# clock_eagle_1.net
KiCad netlist of a schematic drawn in Altium Designer
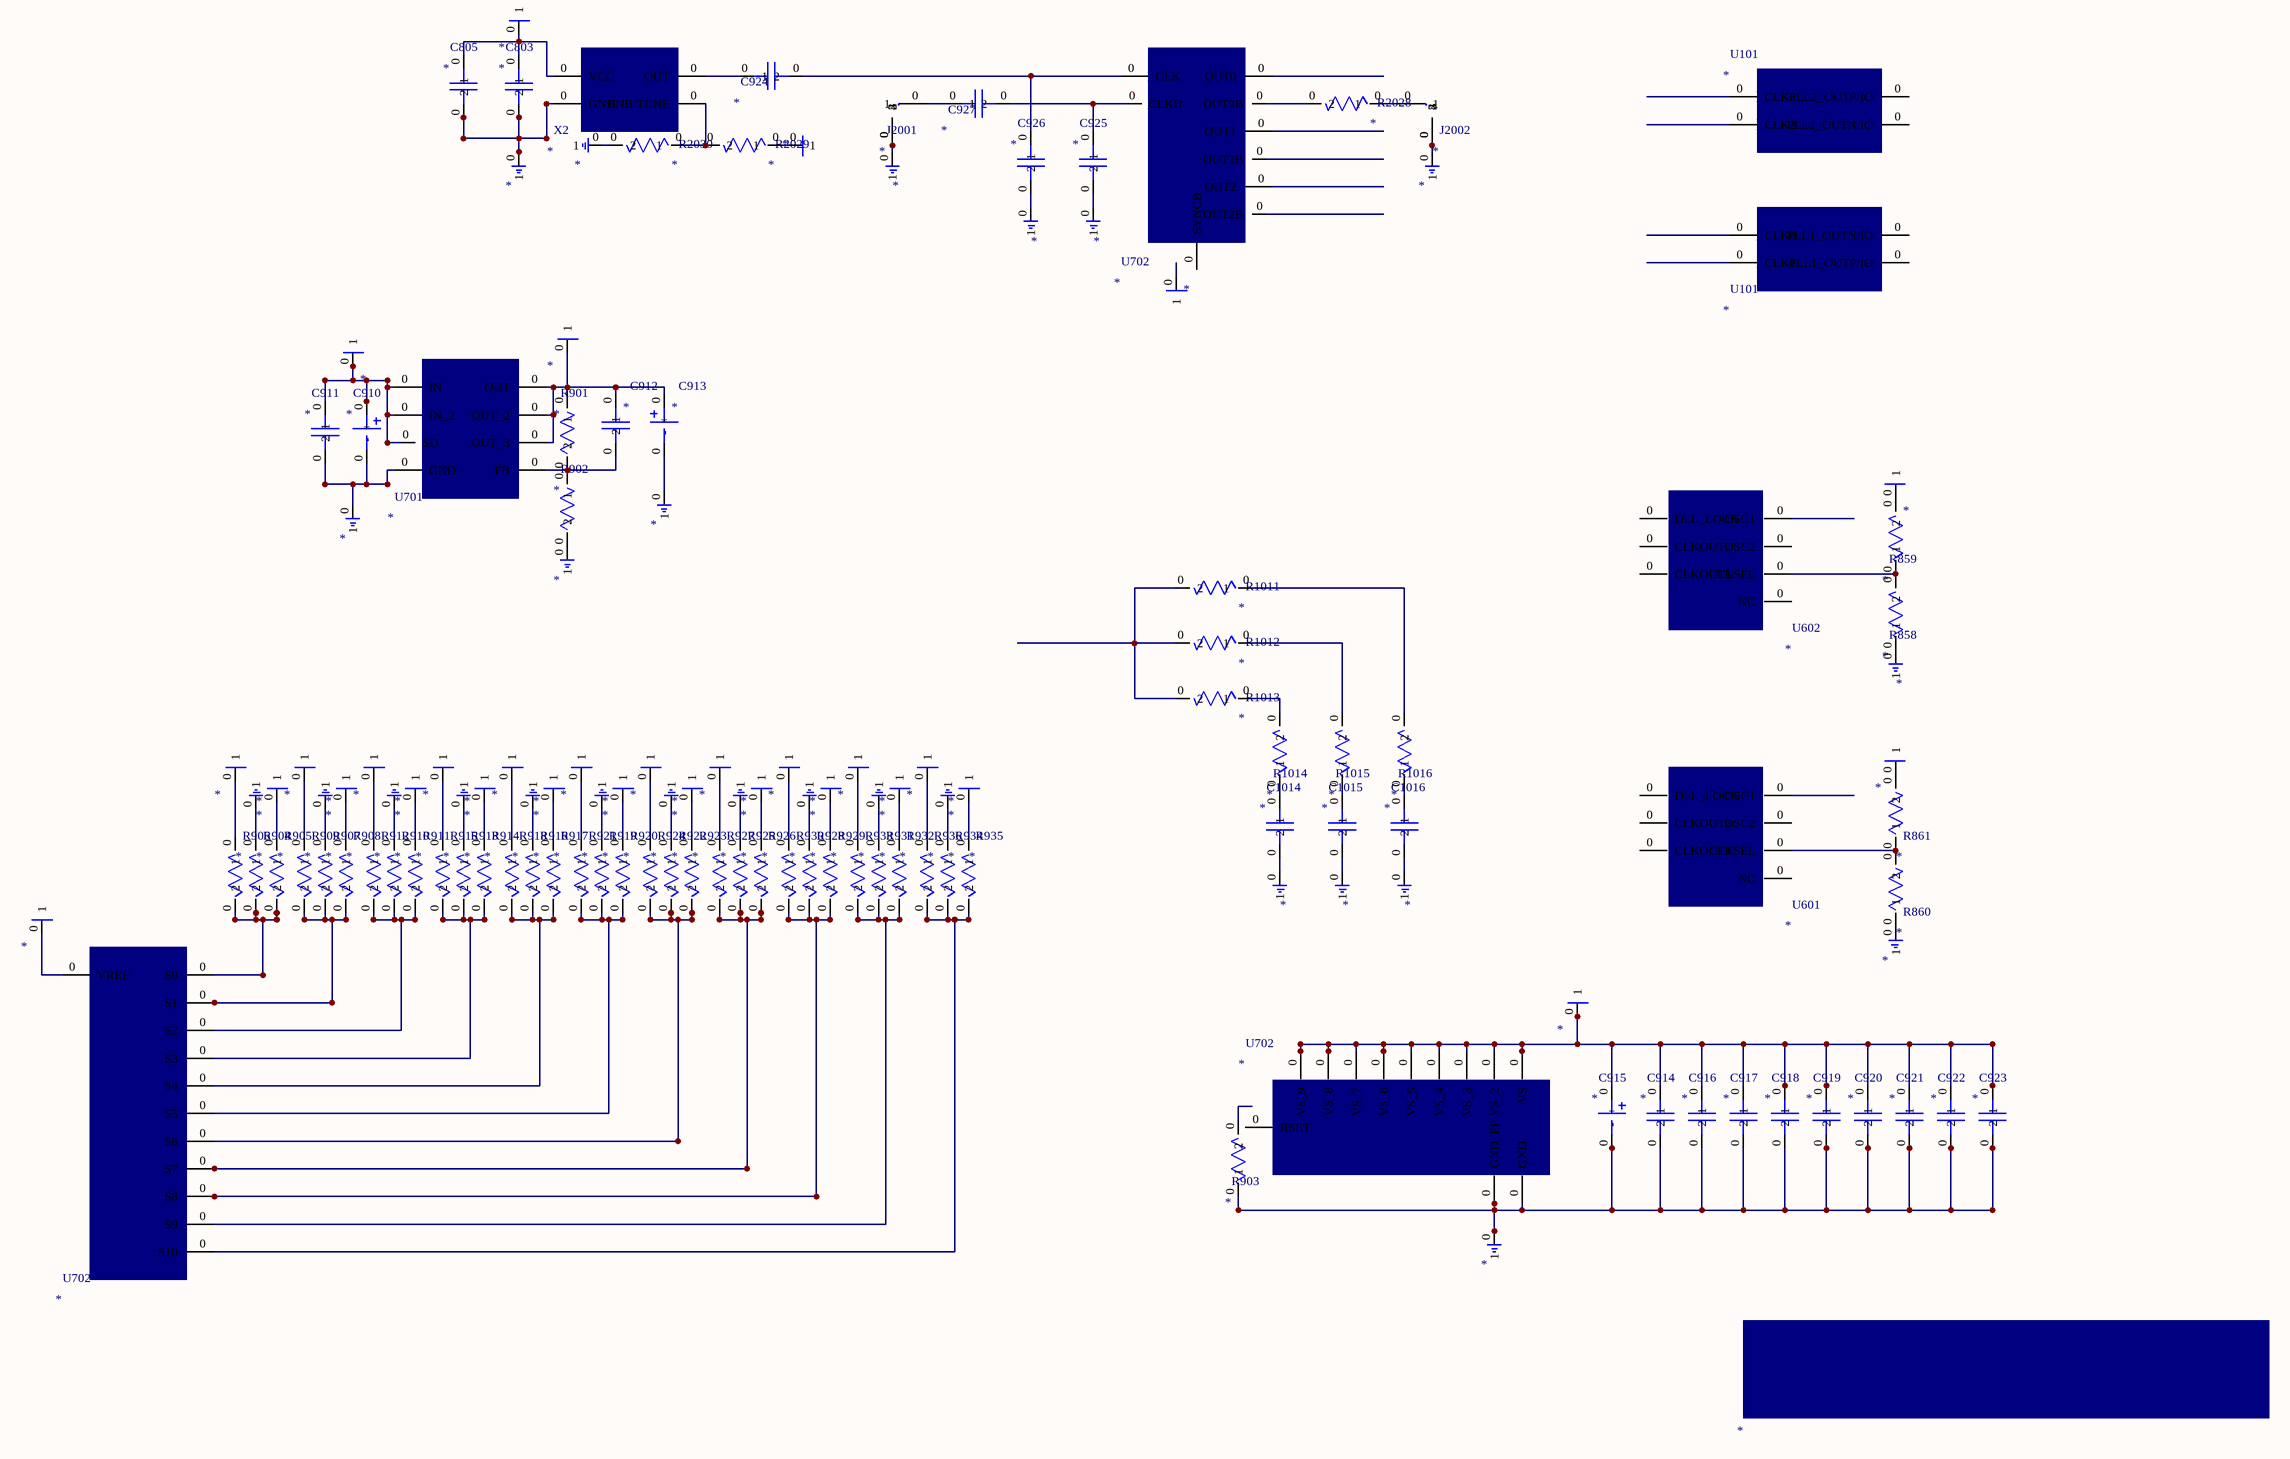
[diagram p0: clock_eagle_1.SchDoc]

(export (version "E")
  (design (tool "Eeschema 10.0.6"))
  (components
    (comp (ref "C803") (value "*") (libsource (lib "") (part "CAPACITOR-1_11")))
    (comp (ref "C805") (value "*") (libsource (lib "") (part "CAPACITOR-1_5")))
    (comp (ref "C910") (value "*") (libsource (lib "openjson") (part "CAPACITOR-2")))
    (comp (ref "C911") (value "*") (libsource (lib "") (part "CAPACITOR-1_12")))
    (comp (ref "C912") (value "*") (libsource (lib "openjson") (part "CAPACITOR-1_MIRRORED")))
    (comp (ref "C913") (value "*") (libsource (lib "openjson") (part "CAPACITOR-2_MIRRORED")))
    (comp (ref "C914") (value "*") (libsource (lib "") (part "CAPACITOR-1_2")))
    (comp (ref "C915") (value "*") (libsource (lib "") (part "CAPACITOR-2_1")))
    (comp (ref "C916") (value "*") (libsource (lib "") (part "CAPACITOR-1_1")))
    (comp (ref "C917") (value "*") (libsource (lib "") (part "CAPACITOR-1_10")))
    (comp (ref "C918") (value "*") (libsource (lib "openjson") (part "CAPACITOR-1")))
    (comp (ref "C919") (value "*") (libsource (lib "") (part "CAPACITOR-1_6")))
    (comp (ref "C920") (value "*") (libsource (lib "") (part "CAPACITOR-1_14")))
    (comp (ref "C921") (value "*") (libsource (lib "") (part "CAPACITOR-1_3")))
    (comp (ref "C922") (value "*") (libsource (lib "") (part "CAPACITOR-1_9")))
    (comp (ref "C923") (value "*") (libsource (lib "") (part "CAPACITOR-1_18")))
    (comp (ref "C924") (value "*") (libsource (lib "") (part "CAPACITOR-1_7")))
    (comp (ref "C925") (value "*") (libsource (lib "") (part "CAPACITOR-1_17")))
    (comp (ref "C926") (value "*") (libsource (lib "") (part "CAPACITOR-1_15")))
    (comp (ref "C927") (value "*") (libsource (lib "") (part "CAPACITOR-1_16")))
    (comp (ref "C1014") (value "*") (libsource (lib "") (part "CAPACITOR-1_4")))
    (comp (ref "C1015") (value "*") (libsource (lib "") (part "CAPACITOR-1_13")))
    (comp (ref "C1016") (value "*") (libsource (lib "") (part "CAPACITOR-1_8")))
    (comp (ref "CVSTITLEBLOCK-1") (value "*") (libsource (lib "openjson") (part "CVSTITLEBLOCK-1")))
    (comp (ref "GENERIC-POWER") (value "*") (libsource (lib "openjson") (part "GENERIC-POWER")))
    (comp (ref "GENERIC-POWER-0") (value "*") (libsource (lib "openjson") (part "GENERIC-POWER")))
    (comp (ref "GENERIC-POWER-5") (value "*") (libsource (lib "openjson") (part "GENERIC-POWER")))
    (comp (ref "GENERIC-POWER-13") (value "*") (libsource (lib "") (part "GENERIC-POWER_1")))
    (comp (ref "GENERIC-POWER-20") (value "*") (libsource (lib "") (part "GENERIC-POWER_1")))
    (comp (ref "GENERIC-POWER-22") (value "*") (libsource (lib "openjson") (part "GENERIC-POWER")))
    (comp (ref "GENERIC-POWER-23") (value "*") (libsource (lib "openjson") (part "GENERIC-POWER")))
    (comp (ref "GENERIC-POWER-25") (value "*") (libsource (lib "openjson") (part "GENERIC-POWER")))
    (comp (ref "GENERIC-POWER-26") (value "*") (libsource (lib "openjson") (part "GENERIC-POWER")))
    (comp (ref "GENERIC-POWER-28") (value "*") (libsource (lib "openjson") (part "GENERIC-POWER")))
    (comp (ref "GENERIC-POWER-29") (value "*") (libsource (lib "openjson") (part "GENERIC-POWER")))
    (comp (ref "GENERIC-POWER-31") (value "*") (libsource (lib "openjson") (part "GENERIC-POWER")))
    (comp (ref "GENERIC-POWER-32") (value "*") (libsource (lib "openjson") (part "GENERIC-POWER")))
    (comp (ref "GENERIC-POWER-34") (value "*") (libsource (lib "openjson") (part "GENERIC-POWER")))
    (comp (ref "GENERIC-POWER-35") (value "*") (libsource (lib "openjson") (part "GENERIC-POWER")))
    (comp (ref "GENERIC-POWER-37") (value "*") (libsource (lib "openjson") (part "GENERIC-POWER")))
    (comp (ref "GENERIC-POWER-38") (value "*") (libsource (lib "openjson") (part "GENERIC-POWER")))
    (comp (ref "GENERIC-POWER-40") (value "*") (libsource (lib "openjson") (part "GENERIC-POWER")))
    (comp (ref "GENERIC-POWER-41") (value "*") (libsource (lib "openjson") (part "GENERIC-POWER")))
    (comp (ref "GENERIC-POWER-43") (value "*") (libsource (lib "openjson") (part "GENERIC-POWER")))
    (comp (ref "GENERIC-POWER-44") (value "*") (libsource (lib "openjson") (part "GENERIC-POWER")))
    (comp (ref "GENERIC-POWER-46") (value "*") (libsource (lib "openjson") (part "GENERIC-POWER")))
    (comp (ref "GENERIC-POWER-47") (value "*") (libsource (lib "openjson") (part "GENERIC-POWER")))
    (comp (ref "GENERIC-POWER-49") (value "*") (libsource (lib "openjson") (part "GENERIC-POWER")))
    (comp (ref "GENERIC-POWER-50") (value "*") (libsource (lib "openjson") (part "GENERIC-POWER")))
    (comp (ref "GENERIC-POWER-52") (value "*") (libsource (lib "openjson") (part "GENERIC-POWER")))
    (comp (ref "GENERIC-POWER-53") (value "*") (libsource (lib "openjson") (part "GENERIC-POWER")))
    (comp (ref "GENERIC-POWER-54") (value "*") (libsource (lib "openjson") (part "GENERIC-POWER")))
    (comp (ref "GENERIC-POWER-55") (value "*") (libsource (lib "openjson") (part "GENERIC-POWER")))
    (comp (ref "GENERIC-POWER_MIRRORED")
      (value "*")
      (libsource (lib "openjson") (part "GENERIC-POWER_MIRRORED"))
    )
    (comp (ref "GENERIC-POWER_MIRRORED-11")
      (value "*")
      (libsource (lib "") (part "GENERIC-POWER_MIRRORED_1"))
    )
    (comp (ref "GND-1") (value "*") (libsource (lib "openjson") (part "GND-1")))
    (comp (ref "GND-1-6") (value "*") (libsource (lib "openjson") (part "GND-1")))
    (comp (ref "GND-1-7") (value "*") (libsource (lib "openjson") (part "GND-1")))
    (comp (ref "GND-1-8") (value "*") (libsource (lib "openjson") (part "GND-1")))
    (comp (ref "GND-1-12") (value "*") (libsource (lib "") (part "GND-1_2")))
    (comp (ref "GND-1-16") (value "*") (libsource (lib "openjson") (part "GND-1")))
    (comp (ref "GND-1-19") (value "*") (libsource (lib "openjson") (part "GND-1")))
    (comp (ref "GND-1-21") (value "*") (libsource (lib "") (part "GND-1_1")))
    (comp (ref "GND-1-24") (value "*") (libsource (lib "") (part "GND-1_1")))
    (comp (ref "GND-1-27") (value "*") (libsource (lib "") (part "GND-1_1")))
    (comp (ref "GND-1-30") (value "*") (libsource (lib "") (part "GND-1_1")))
    (comp (ref "GND-1-33") (value "*") (libsource (lib "") (part "GND-1_1")))
    (comp (ref "GND-1-36") (value "*") (libsource (lib "") (part "GND-1_1")))
    (comp (ref "GND-1-39") (value "*") (libsource (lib "") (part "GND-1_1")))
    (comp (ref "GND-1-42") (value "*") (libsource (lib "") (part "GND-1_1")))
    (comp (ref "GND-1-45") (value "*") (libsource (lib "") (part "GND-1_1")))
    (comp (ref "GND-1-48") (value "*") (libsource (lib "") (part "GND-1_1")))
    (comp (ref "GND-1-51") (value "*") (libsource (lib "") (part "GND-1_1")))
    (comp (ref "GND-1_MIRRORED") (value "*") (libsource (lib "") (part "GND-1_MIRRORED_1")))
    (comp (ref "GND-1_MIRRORED-1") (value "*") (libsource (lib "") (part "GND-1_MIRRORED_1")))
    (comp (ref "GND-1_MIRRORED-2") (value "*") (libsource (lib "") (part "GND-1_MIRRORED_1")))
    (comp (ref "GND-1_MIRRORED-3") (value "*") (libsource (lib "") (part "GND-1_MIRRORED_1")))
    (comp (ref "GND-1_MIRRORED-4") (value "*") (libsource (lib "") (part "GND-1_MIRRORED_2")))
    (comp (ref "GND-1_MIRRORED-10") (value "*") (libsource (lib "openjson") (part "GND-1_MIRRORED")))
    (comp (ref "GND-1_MIRRORED-17") (value "*") (libsource (lib "") (part "GND-1_MIRRORED_1")))
    (comp (ref "GND-1_MIRRORED-18") (value "*") (libsource (lib "") (part "GND-1_MIRRORED_1")))
    (comp (ref "J2001") (value "*") (libsource (lib "openjson") (part "SMA-5")))
    (comp (ref "J2002") (value "*") (libsource (lib "openjson") (part "SMA-5_MIRRORED")))
    (comp (ref "R858") (value "*") (libsource (lib "") (part "RESISTOR-1_MIRRORED_40")))
    (comp (ref "R859") (value "*") (libsource (lib "") (part "RESISTOR-1_MIRRORED_39")))
    (comp (ref "R860") (value "*") (libsource (lib "") (part "RESISTOR-1_3")))
    (comp (ref "R861") (value "*") (libsource (lib "") (part "RESISTOR-1_1")))
    (comp (ref "R901") (value "*") (libsource (lib "openjson") (part "RESISTOR-1")))
    (comp (ref "R902") (value "*") (libsource (lib "") (part "RESISTOR-1_2")))
    (comp (ref "R903") (value "*") (libsource (lib "") (part "RESISTOR-1_MIRRORED_22")))
    (comp (ref "R904") (value "*") (libsource (lib "") (part "RESISTOR-1_MIRRORED_28")))
    (comp (ref "R905") (value "*") (libsource (lib "") (part "RESISTOR-1_MIRRORED_25")))
    (comp (ref "R906") (value "*") (libsource (lib "") (part "RESISTOR-1_MIRRORED_35")))
    (comp (ref "R907") (value "*") (libsource (lib "") (part "RESISTOR-1_MIRRORED_20")))
    (comp (ref "R908") (value "*") (libsource (lib "") (part "RESISTOR-1_MIRRORED_37")))
    (comp (ref "R909") (value "*") (libsource (lib "") (part "RESISTOR-1_MIRRORED_34")))
    (comp (ref "R910") (value "*") (libsource (lib "") (part "RESISTOR-1_MIRRORED_31")))
    (comp (ref "R911") (value "*") (libsource (lib "") (part "RESISTOR-1_MIRRORED_32")))
    (comp (ref "R912") (value "*") (libsource (lib "") (part "RESISTOR-1_MIRRORED_38")))
    (comp (ref "R913") (value "*") (libsource (lib "") (part "RESISTOR-1_MIRRORED_30")))
    (comp (ref "R914") (value "*") (libsource (lib "") (part "RESISTOR-1_MIRRORED_1")))
    (comp (ref "R915") (value "*") (libsource (lib "") (part "RESISTOR-1_MIRRORED_4")))
    (comp (ref "R916") (value "*") (libsource (lib "") (part "RESISTOR-1_MIRRORED_21")))
    (comp (ref "R917") (value "*") (libsource (lib "") (part "RESISTOR-1_MIRRORED_8")))
    (comp (ref "R918") (value "*") (libsource (lib "") (part "RESISTOR-1_MIRRORED_10")))
    (comp (ref "R919") (value "*") (libsource (lib "") (part "RESISTOR-1_MIRRORED_18")))
    (comp (ref "R920") (value "*") (libsource (lib "") (part "RESISTOR-1_MIRRORED_11")))
    (comp (ref "R921") (value "*") (libsource (lib "") (part "RESISTOR-1_MIRRORED_15")))
    (comp (ref "R922") (value "*") (libsource (lib "") (part "RESISTOR-1_MIRRORED_16")))
    (comp (ref "R923") (value "*") (libsource (lib "") (part "RESISTOR-1_MIRRORED_29")))
    (comp (ref "R924") (value "*") (libsource (lib "") (part "RESISTOR-1_MIRRORED_7")))
    (comp (ref "R925") (value "*") (libsource (lib "") (part "RESISTOR-1_MIRRORED_5")))
    (comp (ref "R926") (value "*") (libsource (lib "openjson") (part "RESISTOR-1_MIRRORED")))
    (comp (ref "R927") (value "*") (libsource (lib "") (part "RESISTOR-1_MIRRORED_36")))
    (comp (ref "R928") (value "*") (libsource (lib "") (part "RESISTOR-1_MIRRORED_12")))
    (comp (ref "R929") (value "*") (libsource (lib "") (part "RESISTOR-1_MIRRORED_17")))
    (comp (ref "R930") (value "*") (libsource (lib "") (part "RESISTOR-1_MIRRORED_27")))
    (comp (ref "R931") (value "*") (libsource (lib "") (part "RESISTOR-1_MIRRORED_24")))
    (comp (ref "R932") (value "*") (libsource (lib "") (part "RESISTOR-1_MIRRORED_33")))
    (comp (ref "R933") (value "*") (libsource (lib "") (part "RESISTOR-1_MIRRORED_41")))
    (comp (ref "R934") (value "*") (libsource (lib "") (part "RESISTOR-1_MIRRORED_42")))
    (comp (ref "R935") (value "*") (libsource (lib "") (part "RESISTOR-1_MIRRORED_14")))
    (comp (ref "R936") (value "*") (libsource (lib "") (part "RESISTOR-1_MIRRORED_23")))
    (comp (ref "R1011") (value "*") (libsource (lib "") (part "RESISTOR-1_MIRRORED_26")))
    (comp (ref "R1012") (value "*") (libsource (lib "") (part "RESISTOR-1_MIRRORED_44")))
    (comp (ref "R1013") (value "*") (libsource (lib "") (part "RESISTOR-1_MIRRORED_3")))
    (comp (ref "R1014") (value "*") (libsource (lib "") (part "RESISTOR-1_MIRRORED_13")))
    (comp (ref "R1015") (value "*") (libsource (lib "") (part "RESISTOR-1_MIRRORED_43")))
    (comp (ref "R1016") (value "*") (libsource (lib "") (part "RESISTOR-1_MIRRORED_19")))
    (comp (ref "R2028") (value "*") (libsource (lib "") (part "RESISTOR-1_MIRRORED_6")))
    (comp (ref "R2029") (value "*") (libsource (lib "") (part "RESISTOR-1_MIRRORED_2")))
    (comp (ref "R2030") (value "*") (libsource (lib "") (part "RESISTOR-1_MIRRORED_9")))
    (comp (ref "U101") (value "*") (libsource (lib "openjson") (part "EP1C12-PQ240-CLKA")))
    (comp (ref "U101-9") (value "*") (libsource (lib "openjson") (part "EP1C12-PQ240-CLKB_MIRRORED")))
    (comp (ref "U601") (value "*") (libsource (lib "openjson") (part "AD986X-CLK_MIRRORED")))
    (comp (ref "U602") (value "*") (libsource (lib "") (part "AD986X-CLK_MIRRORED_1")))
    (comp (ref "U701") (value "*") (libsource (lib "openjson") (part "ADP3336")))
    (comp (ref "U702") (value "*") (libsource (lib "openjson") (part "AD9513-CLK")))
    (comp (ref "U702-14") (value "*") (libsource (lib "openjson") (part "AD9513-CTRL")))
    (comp (ref "U702-15") (value "*") (libsource (lib "openjson") (part "AD9513-PWR")))
    (comp (ref "X2") (value "*") (libsource (lib "openjson") (part "VCTCXO")))
  )
  (nets
    (net (code "1") (name "Net-(C803-1)") (class "Default")
      (node (ref "C803") (pin "0") (pinfunction "1_0") (pintype "passive"))
      (node (ref "C805") (pin "0") (pinfunction "1_0") (pintype "passive"))
      (node (ref "GENERIC-POWER") (pin "0") (pinfunction "1_0") (pintype "passive"))
      (node (ref "X2") (pin "0") (pinfunction "VCC_0") (pintype "passive"))
    )
    (net (code "2") (name "Net-(C803-2)") (class "Default")
      (node (ref "C803") (pin "0") (pinfunction "2_0") (pintype "passive"))
      (node (ref "C805") (pin "0") (pinfunction "2_0") (pintype "passive"))
      (node (ref "GND-1") (pin "0") (pinfunction "1_0") (pintype "passive"))
      (node (ref "X2") (pin "0") (pinfunction "GND_0") (pintype "passive"))
    )
    (net (code "3") (name "Net-(C910-+)") (class "Default")
      (node (ref "C910") (pin "0") (pinfunction "+_0") (pintype "passive"))
      (node (ref "C911") (pin "0") (pinfunction "1_0") (pintype "passive"))
      (node (ref "GENERIC-POWER_MIRRORED") (pin "0") (pinfunction "1_0") (pintype "passive"))
      (node (ref "U701") (pin "0") (pinfunction "IN_0") (pintype "passive"))
    )
    (net (code "4") (name "Net-(C910--)") (class "Default")
      (node (ref "C910") (pin "0") (pinfunction "-_0") (pintype "passive"))
      (node (ref "C911") (pin "0") (pinfunction "2_0") (pintype "passive"))
      (node (ref "GND-1-6") (pin "0") (pinfunction "1_0") (pintype "passive"))
      (node (ref "U701") (pin "0") (pinfunction "GND_0") (pintype "passive"))
    )
    (net (code "5") (name "Net-(C912-1)") (class "Default")
      (node (ref "C912") (pin "0") (pinfunction "1_0") (pintype "passive"))
      (node (ref "C913") (pin "0") (pinfunction "+_0") (pintype "passive"))
      (node (ref "GENERIC-POWER-5") (pin "0") (pinfunction "1_0") (pintype "passive"))
      (node (ref "R901") (pin "0") (pinfunction "1_0") (pintype "passive"))
      (node (ref "U701") (pin "0") (pinfunction "OUT_0") (pintype "passive"))
    )
    (net (code "6") (name "Net-(C912-2)") (class "Default")
      (node (ref "C912") (pin "0") (pinfunction "2_0") (pintype "passive"))
      (node (ref "R901") (pin "0") (pinfunction "2_0") (pintype "passive"))
      (node (ref "R902") (pin "0") (pinfunction "1_0") (pintype "passive"))
      (node (ref "U701") (pin "0") (pinfunction "FB_0") (pintype "passive"))
    )
    (net (code "7") (name "Net-(C913--)") (class "Default")
      (node (ref "C913") (pin "0") (pinfunction "-_0") (pintype "passive"))
      (node (ref "GND-1-8") (pin "0") (pinfunction "1_0") (pintype "passive"))
    )
    (net (code "8") (name "Net-(C914-1)") (class "Default")
      (node (ref "C914") (pin "0") (pinfunction "1_0") (pintype "passive"))
      (node (ref "C915") (pin "0") (pinfunction "+_0") (pintype "passive"))
      (node (ref "C916") (pin "0") (pinfunction "1_0") (pintype "passive"))
      (node (ref "C917") (pin "0") (pinfunction "1_0") (pintype "passive"))
      (node (ref "C918") (pin "0") (pinfunction "1_0") (pintype "passive"))
      (node (ref "C919") (pin "0") (pinfunction "1_0") (pintype "passive"))
      (node (ref "C920") (pin "0") (pinfunction "1_0") (pintype "passive"))
      (node (ref "C921") (pin "0") (pinfunction "1_0") (pintype "passive"))
      (node (ref "C922") (pin "0") (pinfunction "1_0") (pintype "passive"))
      (node (ref "C923") (pin "0") (pinfunction "1_0") (pintype "passive"))
      (node (ref "GENERIC-POWER-55") (pin "0") (pinfunction "1_0") (pintype "passive"))
      (node (ref "U702-15") (pin "0") (pinfunction "VS_9_0") (pintype "passive"))
    )
    (net (code "9") (name "Net-(C914-2)") (class "Default")
      (node (ref "C914") (pin "0") (pinfunction "2_0") (pintype "passive"))
      (node (ref "C915") (pin "0") (pinfunction "-_0") (pintype "passive"))
      (node (ref "C916") (pin "0") (pinfunction "2_0") (pintype "passive"))
      (node (ref "C917") (pin "0") (pinfunction "2_0") (pintype "passive"))
      (node (ref "C918") (pin "0") (pinfunction "2_0") (pintype "passive"))
      (node (ref "C919") (pin "0") (pinfunction "2_0") (pintype "passive"))
      (node (ref "C920") (pin "0") (pinfunction "2_0") (pintype "passive"))
      (node (ref "C921") (pin "0") (pinfunction "2_0") (pintype "passive"))
      (node (ref "C922") (pin "0") (pinfunction "2_0") (pintype "passive"))
      (node (ref "C923") (pin "0") (pinfunction "2_0") (pintype "passive"))
      (node (ref "GND-1-16") (pin "0") (pinfunction "1_0") (pintype "passive"))
      (node (ref "R903") (pin "0") (pinfunction "1_0") (pintype "passive"))
      (node (ref "U702-15") (pin "0") (pinfunction "GND_0") (pintype "passive"))
    )
    (net (code "10") (name "Net-(C924-1)") (class "Default")
      (node (ref "C924") (pin "0") (pinfunction "1_0") (pintype "passive"))
      (node (ref "X2") (pin "0") (pinfunction "OUT_0") (pintype "passive"))
    )
    (net (code "11") (name "Net-(C924-2)") (class "Default")
      (node (ref "C924") (pin "0") (pinfunction "2_0") (pintype "passive"))
      (node (ref "C926") (pin "0") (pinfunction "1_0") (pintype "passive"))
      (node (ref "U702") (pin "0") (pinfunction "CLK_0") (pintype "passive"))
    )
    (net (code "12") (name "Net-(C925-1)") (class "Default")
      (node (ref "C925") (pin "0") (pinfunction "1_0") (pintype "passive"))
      (node (ref "C927") (pin "0") (pinfunction "2_0") (pintype "passive"))
      (node (ref "U702") (pin "0") (pinfunction "CLKB_0") (pintype "passive"))
    )
    (net (code "13") (name "Net-(C925-2)") (class "Default")
      (node (ref "C925") (pin "0") (pinfunction "2_0") (pintype "passive"))
      (node (ref "GND-1_MIRRORED-17") (pin "0") (pinfunction "1_0") (pintype "passive"))
    )
    (net (code "14") (name "Net-(C926-2)") (class "Default")
      (node (ref "C926") (pin "0") (pinfunction "2_0") (pintype "passive"))
      (node (ref "GND-1_MIRRORED-18") (pin "0") (pinfunction "1_0") (pintype "passive"))
    )
    (net (code "15") (name "Net-(C927-1)") (class "Default")
      (node (ref "C927") (pin "0") (pinfunction "1_0") (pintype "passive"))
      (node (ref "J2001") (pin "0") (pinfunction "1_0") (pintype "passive"))
    )
    (net (code "16") (name "Net-(C1014-1)") (class "Default")
      (node (ref "C1014") (pin "0") (pinfunction "1_0") (pintype "passive"))
      (node (ref "R1014") (pin "0") (pinfunction "1_0") (pintype "passive"))
    )
    (net (code "17") (name "Net-(C1014-2)") (class "Default")
      (node (ref "C1014") (pin "0") (pinfunction "2_0") (pintype "passive"))
      (node (ref "GND-1_MIRRORED") (pin "0") (pinfunction "1_0") (pintype "passive"))
    )
    (net (code "18") (name "Net-(C1015-1)") (class "Default")
      (node (ref "C1015") (pin "0") (pinfunction "1_0") (pintype "passive"))
      (node (ref "R1015") (pin "0") (pinfunction "1_0") (pintype "passive"))
    )
    (net (code "19") (name "Net-(C1015-2)") (class "Default")
      (node (ref "C1015") (pin "0") (pinfunction "2_0") (pintype "passive"))
      (node (ref "GND-1_MIRRORED-1") (pin "0") (pinfunction "1_0") (pintype "passive"))
    )
    (net (code "20") (name "Net-(C1016-1)") (class "Default")
      (node (ref "C1016") (pin "0") (pinfunction "1_0") (pintype "passive"))
      (node (ref "R1016") (pin "0") (pinfunction "1_0") (pintype "passive"))
    )
    (net (code "21") (name "Net-(C1016-2)") (class "Default")
      (node (ref "C1016") (pin "0") (pinfunction "2_0") (pintype "passive"))
      (node (ref "GND-1_MIRRORED-2") (pin "0") (pinfunction "1_0") (pintype "passive"))
    )
    (net (code "22") (name "Net-(GENERIC-POWER-0-1)") (class "Default")
      (node (ref "GENERIC-POWER-0") (pin "0") (pinfunction "1_0") (pintype "passive"))
      (node (ref "R2029") (pin "0") (pinfunction "1_0") (pintype "passive"))
    )
    (net (code "23") (name "Net-(GENERIC-POWER-13-1)") (class "Default")
      (node (ref "GENERIC-POWER-13") (pin "0") (pinfunction "1_0") (pintype "passive"))
      (node (ref "R861") (pin "0") (pinfunction "2_0") (pintype "passive"))
    )
    (net (code "24") (name "Net-(GENERIC-POWER-22-1)") (class "Default")
      (node (ref "GENERIC-POWER-22") (pin "0") (pinfunction "1_0") (pintype "passive"))
      (node (ref "R905") (pin "0") (pinfunction "1_0") (pintype "passive"))
    )
    (net (code "25") (name "Net-(GENERIC-POWER-23-1)") (class "Default")
      (node (ref "GENERIC-POWER-23") (pin "0") (pinfunction "1_0") (pintype "passive"))
      (node (ref "R906") (pin "0") (pinfunction "1_0") (pintype "passive"))
    )
    (net (code "26") (name "Net-(GENERIC-POWER-25-1)") (class "Default")
      (node (ref "GENERIC-POWER-25") (pin "0") (pinfunction "1_0") (pintype "passive"))
      (node (ref "R908") (pin "0") (pinfunction "1_0") (pintype "passive"))
    )
    (net (code "27") (name "Net-(GENERIC-POWER-26-1)") (class "Default")
      (node (ref "GENERIC-POWER-26") (pin "0") (pinfunction "1_0") (pintype "passive"))
      (node (ref "R909") (pin "0") (pinfunction "1_0") (pintype "passive"))
    )
    (net (code "28") (name "Net-(GENERIC-POWER-28-1)") (class "Default")
      (node (ref "GENERIC-POWER-28") (pin "0") (pinfunction "1_0") (pintype "passive"))
      (node (ref "R911") (pin "0") (pinfunction "1_0") (pintype "passive"))
    )
    (net (code "29") (name "Net-(GENERIC-POWER-29-1)") (class "Default")
      (node (ref "GENERIC-POWER-29") (pin "0") (pinfunction "1_0") (pintype "passive"))
      (node (ref "R912") (pin "0") (pinfunction "1_0") (pintype "passive"))
    )
    (net (code "30") (name "Net-(GENERIC-POWER-31-1)") (class "Default")
      (node (ref "GENERIC-POWER-31") (pin "0") (pinfunction "1_0") (pintype "passive"))
      (node (ref "R914") (pin "0") (pinfunction "1_0") (pintype "passive"))
    )
    (net (code "31") (name "Net-(GENERIC-POWER-32-1)") (class "Default")
      (node (ref "GENERIC-POWER-32") (pin "0") (pinfunction "1_0") (pintype "passive"))
      (node (ref "R915") (pin "0") (pinfunction "1_0") (pintype "passive"))
    )
    (net (code "32") (name "Net-(GENERIC-POWER-34-1)") (class "Default")
      (node (ref "GENERIC-POWER-34") (pin "0") (pinfunction "1_0") (pintype "passive"))
      (node (ref "R917") (pin "0") (pinfunction "1_0") (pintype "passive"))
    )
    (net (code "33") (name "Net-(GENERIC-POWER-35-1)") (class "Default")
      (node (ref "GENERIC-POWER-35") (pin "0") (pinfunction "1_0") (pintype "passive"))
      (node (ref "R918") (pin "0") (pinfunction "1_0") (pintype "passive"))
    )
    (net (code "34") (name "Net-(GENERIC-POWER-37-1)") (class "Default")
      (node (ref "GENERIC-POWER-37") (pin "0") (pinfunction "1_0") (pintype "passive"))
      (node (ref "R920") (pin "0") (pinfunction "1_0") (pintype "passive"))
    )
    (net (code "35") (name "Net-(GENERIC-POWER-38-1)") (class "Default")
      (node (ref "GENERIC-POWER-38") (pin "0") (pinfunction "1_0") (pintype "passive"))
      (node (ref "R921") (pin "0") (pinfunction "1_0") (pintype "passive"))
    )
    (net (code "36") (name "Net-(GENERIC-POWER-40-1)") (class "Default")
      (node (ref "GENERIC-POWER-40") (pin "0") (pinfunction "1_0") (pintype "passive"))
      (node (ref "R923") (pin "0") (pinfunction "1_0") (pintype "passive"))
    )
    (net (code "37") (name "Net-(GENERIC-POWER-41-1)") (class "Default")
      (node (ref "GENERIC-POWER-41") (pin "0") (pinfunction "1_0") (pintype "passive"))
      (node (ref "R924") (pin "0") (pinfunction "1_0") (pintype "passive"))
    )
    (net (code "38") (name "Net-(GENERIC-POWER-43-1)") (class "Default")
      (node (ref "GENERIC-POWER-43") (pin "0") (pinfunction "1_0") (pintype "passive"))
      (node (ref "R926") (pin "0") (pinfunction "1_0") (pintype "passive"))
    )
    (net (code "39") (name "Net-(GENERIC-POWER-44-1)") (class "Default")
      (node (ref "GENERIC-POWER-44") (pin "0") (pinfunction "1_0") (pintype "passive"))
      (node (ref "R927") (pin "0") (pinfunction "1_0") (pintype "passive"))
    )
    (net (code "40") (name "Net-(GENERIC-POWER-46-1)") (class "Default")
      (node (ref "GENERIC-POWER-46") (pin "0") (pinfunction "1_0") (pintype "passive"))
      (node (ref "R929") (pin "0") (pinfunction "1_0") (pintype "passive"))
    )
    (net (code "41") (name "Net-(GENERIC-POWER-47-1)") (class "Default")
      (node (ref "GENERIC-POWER-47") (pin "0") (pinfunction "1_0") (pintype "passive"))
      (node (ref "R930") (pin "0") (pinfunction "1_0") (pintype "passive"))
    )
    (net (code "42") (name "Net-(GENERIC-POWER-49-1)") (class "Default")
      (node (ref "GENERIC-POWER-49") (pin "0") (pinfunction "1_0") (pintype "passive"))
      (node (ref "R932") (pin "0") (pinfunction "1_0") (pintype "passive"))
    )
    (net (code "43") (name "Net-(GENERIC-POWER-50-1)") (class "Default")
      (node (ref "GENERIC-POWER-50") (pin "0") (pinfunction "1_0") (pintype "passive"))
      (node (ref "R933") (pin "0") (pinfunction "1_0") (pintype "passive"))
    )
    (net (code "44") (name "Net-(GENERIC-POWER-52-1)") (class "Default")
      (node (ref "GENERIC-POWER-52") (pin "0") (pinfunction "1_0") (pintype "passive"))
      (node (ref "R935") (pin "0") (pinfunction "1_0") (pintype "passive"))
    )
    (net (code "45") (name "Net-(GENERIC-POWER-53-1)") (class "Default")
      (node (ref "GENERIC-POWER-53") (pin "0") (pinfunction "1_0") (pintype "passive"))
      (node (ref "R936") (pin "0") (pinfunction "1_0") (pintype "passive"))
    )
    (net (code "46") (name "Net-(GENERIC-POWER-54-1)") (class "Default")
      (node (ref "GENERIC-POWER-54") (pin "0") (pinfunction "1_0") (pintype "passive"))
      (node (ref "U702-14") (pin "0") (pinfunction "VREF_0") (pintype "passive"))
    )
    (net (code "47") (name "Net-(GENERIC-POWER_MIRRORED-11-1)") (class "Default")
      (node (ref "GENERIC-POWER_MIRRORED-11") (pin "0") (pinfunction "1_0") (pintype "passive"))
      (node (ref "R859") (pin "0") (pinfunction "2_0") (pintype "passive"))
    )
    (net (code "48") (name "Net-(GND-1-7-1)") (class "Default")
      (node (ref "GND-1-7") (pin "0") (pinfunction "1_0") (pintype "passive"))
      (node (ref "R902") (pin "0") (pinfunction "2_0") (pintype "passive"))
    )
    (net (code "49") (name "Net-(GND-1-12-1)") (class "Default")
      (node (ref "GND-1-12") (pin "0") (pinfunction "1_0") (pintype "passive"))
      (node (ref "R860") (pin "0") (pinfunction "1_0") (pintype "passive"))
    )
    (net (code "50") (name "Net-(GND-1-19-1)") (class "Default")
      (node (ref "GND-1-19") (pin "0") (pinfunction "1_0") (pintype "passive"))
      (node (ref "J2002") (pin "0") (pinfunction "2_0") (pintype "passive"))
    )
    (net (code "51") (name "Net-(GND-1-21-1)") (class "Default")
      (node (ref "GND-1-21") (pin "0") (pinfunction "1_0") (pintype "passive"))
      (node (ref "R904") (pin "0") (pinfunction "1_0") (pintype "passive"))
    )
    (net (code "52") (name "Net-(GND-1-24-1)") (class "Default")
      (node (ref "GND-1-24") (pin "0") (pinfunction "1_0") (pintype "passive"))
      (node (ref "R907") (pin "0") (pinfunction "1_0") (pintype "passive"))
    )
    (net (code "53") (name "Net-(GND-1-27-1)") (class "Default")
      (node (ref "GND-1-27") (pin "0") (pinfunction "1_0") (pintype "passive"))
      (node (ref "R910") (pin "0") (pinfunction "1_0") (pintype "passive"))
    )
    (net (code "54") (name "Net-(GND-1-30-1)") (class "Default")
      (node (ref "GND-1-30") (pin "0") (pinfunction "1_0") (pintype "passive"))
      (node (ref "R913") (pin "0") (pinfunction "1_0") (pintype "passive"))
    )
    (net (code "55") (name "Net-(GND-1-33-1)") (class "Default")
      (node (ref "GND-1-33") (pin "0") (pinfunction "1_0") (pintype "passive"))
      (node (ref "R916") (pin "0") (pinfunction "1_0") (pintype "passive"))
    )
    (net (code "56") (name "Net-(GND-1-36-1)") (class "Default")
      (node (ref "GND-1-36") (pin "0") (pinfunction "1_0") (pintype "passive"))
      (node (ref "R919") (pin "0") (pinfunction "1_0") (pintype "passive"))
    )
    (net (code "57") (name "Net-(GND-1-39-1)") (class "Default")
      (node (ref "GND-1-39") (pin "0") (pinfunction "1_0") (pintype "passive"))
      (node (ref "R922") (pin "0") (pinfunction "1_0") (pintype "passive"))
    )
    (net (code "58") (name "Net-(GND-1-42-1)") (class "Default")
      (node (ref "GND-1-42") (pin "0") (pinfunction "1_0") (pintype "passive"))
      (node (ref "R925") (pin "0") (pinfunction "1_0") (pintype "passive"))
    )
    (net (code "59") (name "Net-(GND-1-45-1)") (class "Default")
      (node (ref "GND-1-45") (pin "0") (pinfunction "1_0") (pintype "passive"))
      (node (ref "R928") (pin "0") (pinfunction "1_0") (pintype "passive"))
    )
    (net (code "60") (name "Net-(GND-1-48-1)") (class "Default")
      (node (ref "GND-1-48") (pin "0") (pinfunction "1_0") (pintype "passive"))
      (node (ref "R931") (pin "0") (pinfunction "1_0") (pintype "passive"))
    )
    (net (code "61") (name "Net-(GND-1-51-1)") (class "Default")
      (node (ref "GND-1-51") (pin "0") (pinfunction "1_0") (pintype "passive"))
      (node (ref "R934") (pin "0") (pinfunction "1_0") (pintype "passive"))
    )
    (net (code "62") (name "Net-(GND-1_MIRRORED-3-1)") (class "Default")
      (node (ref "GND-1_MIRRORED-3") (pin "0") (pinfunction "1_0") (pintype "passive"))
      (node (ref "J2001") (pin "0") (pinfunction "2_0") (pintype "passive"))
    )
    (net (code "63") (name "Net-(GND-1_MIRRORED-4-1)") (class "Default")
      (node (ref "GND-1_MIRRORED-4") (pin "0") (pinfunction "1_0") (pintype "passive"))
      (node (ref "R2030") (pin "0") (pinfunction "2_0") (pintype "passive"))
    )
    (net (code "64") (name "Net-(GND-1_MIRRORED-10-1)") (class "Default")
      (node (ref "GND-1_MIRRORED-10") (pin "0") (pinfunction "1_0") (pintype "passive"))
      (node (ref "R858") (pin "0") (pinfunction "1_0") (pintype "passive"))
    )
    (net (code "65") (name "Net-(J2002-1)") (class "Default")
      (node (ref "J2002") (pin "0") (pinfunction "1_0") (pintype "passive"))
      (node (ref "R2028") (pin "0") (pinfunction "1_0") (pintype "passive"))
    )
    (net (code "66") (name "Net-(R858-2)") (class "Default")
      (node (ref "R858") (pin "0") (pinfunction "2_0") (pintype "passive"))
      (node (ref "R859") (pin "0") (pinfunction "1_0") (pintype "passive"))
      (node (ref "U602") (pin "0") (pinfunction "CLKSEL_0") (pintype "passive"))
    )
    (net (code "67") (name "Net-(R860-2)") (class "Default")
      (node (ref "R860") (pin "0") (pinfunction "2_0") (pintype "passive"))
      (node (ref "R861") (pin "0") (pinfunction "1_0") (pintype "passive"))
      (node (ref "U601") (pin "0") (pinfunction "CLKSEL_0") (pintype "passive"))
    )
    (net (code "68") (name "Net-(R904-2)") (class "Default")
      (node (ref "R904") (pin "0") (pinfunction "2_0") (pintype "passive"))
      (node (ref "R905") (pin "0") (pinfunction "2_0") (pintype "passive"))
      (node (ref "R906") (pin "0") (pinfunction "2_0") (pintype "passive"))
      (node (ref "U702-14") (pin "0") (pinfunction "S0_0") (pintype "passive"))
    )
    (net (code "69") (name "Net-(R907-2)") (class "Default")
      (node (ref "R907") (pin "0") (pinfunction "2_0") (pintype "passive"))
      (node (ref "R908") (pin "0") (pinfunction "2_0") (pintype "passive"))
      (node (ref "R909") (pin "0") (pinfunction "2_0") (pintype "passive"))
      (node (ref "U702-14") (pin "0") (pinfunction "S1_0") (pintype "passive"))
    )
    (net (code "70") (name "Net-(R910-2)") (class "Default")
      (node (ref "R910") (pin "0") (pinfunction "2_0") (pintype "passive"))
      (node (ref "R911") (pin "0") (pinfunction "2_0") (pintype "passive"))
      (node (ref "R912") (pin "0") (pinfunction "2_0") (pintype "passive"))
      (node (ref "U702-14") (pin "0") (pinfunction "S2_0") (pintype "passive"))
    )
    (net (code "71") (name "Net-(R913-2)") (class "Default")
      (node (ref "R913") (pin "0") (pinfunction "2_0") (pintype "passive"))
      (node (ref "R914") (pin "0") (pinfunction "2_0") (pintype "passive"))
      (node (ref "R915") (pin "0") (pinfunction "2_0") (pintype "passive"))
      (node (ref "U702-14") (pin "0") (pinfunction "S3_0") (pintype "passive"))
    )
    (net (code "72") (name "Net-(R916-2)") (class "Default")
      (node (ref "R916") (pin "0") (pinfunction "2_0") (pintype "passive"))
      (node (ref "R917") (pin "0") (pinfunction "2_0") (pintype "passive"))
      (node (ref "R918") (pin "0") (pinfunction "2_0") (pintype "passive"))
      (node (ref "U702-14") (pin "0") (pinfunction "S4_0") (pintype "passive"))
    )
    (net (code "73") (name "Net-(R919-2)") (class "Default")
      (node (ref "R919") (pin "0") (pinfunction "2_0") (pintype "passive"))
      (node (ref "R920") (pin "0") (pinfunction "2_0") (pintype "passive"))
      (node (ref "R921") (pin "0") (pinfunction "2_0") (pintype "passive"))
      (node (ref "U702-14") (pin "0") (pinfunction "S5_0") (pintype "passive"))
    )
    (net (code "74") (name "Net-(R922-2)") (class "Default")
      (node (ref "R922") (pin "0") (pinfunction "2_0") (pintype "passive"))
      (node (ref "R923") (pin "0") (pinfunction "2_0") (pintype "passive"))
      (node (ref "R924") (pin "0") (pinfunction "2_0") (pintype "passive"))
      (node (ref "U702-14") (pin "0") (pinfunction "S6_0") (pintype "passive"))
    )
    (net (code "75") (name "Net-(R925-2)") (class "Default")
      (node (ref "R925") (pin "0") (pinfunction "2_0") (pintype "passive"))
      (node (ref "R926") (pin "0") (pinfunction "2_0") (pintype "passive"))
      (node (ref "R927") (pin "0") (pinfunction "2_0") (pintype "passive"))
      (node (ref "U702-14") (pin "0") (pinfunction "S7_0") (pintype "passive"))
    )
    (net (code "76") (name "Net-(R928-2)") (class "Default")
      (node (ref "R928") (pin "0") (pinfunction "2_0") (pintype "passive"))
      (node (ref "R929") (pin "0") (pinfunction "2_0") (pintype "passive"))
      (node (ref "R930") (pin "0") (pinfunction "2_0") (pintype "passive"))
      (node (ref "U702-14") (pin "0") (pinfunction "S8_0") (pintype "passive"))
    )
    (net (code "77") (name "Net-(R931-2)") (class "Default")
      (node (ref "R931") (pin "0") (pinfunction "2_0") (pintype "passive"))
      (node (ref "R932") (pin "0") (pinfunction "2_0") (pintype "passive"))
      (node (ref "R933") (pin "0") (pinfunction "2_0") (pintype "passive"))
      (node (ref "U702-14") (pin "0") (pinfunction "S9_0") (pintype "passive"))
    )
    (net (code "78") (name "Net-(R934-2)") (class "Default")
      (node (ref "R934") (pin "0") (pinfunction "2_0") (pintype "passive"))
      (node (ref "R935") (pin "0") (pinfunction "2_0") (pintype "passive"))
      (node (ref "R936") (pin "0") (pinfunction "2_0") (pintype "passive"))
      (node (ref "U702-14") (pin "0") (pinfunction "S10_0") (pintype "passive"))
    )
    (net (code "79") (name "Net-(R1011-1)") (class "Default")
      (node (ref "R1011") (pin "0") (pinfunction "1_0") (pintype "passive"))
      (node (ref "R1016") (pin "0") (pinfunction "2_0") (pintype "passive"))
    )
    (net (code "80") (name "Net-(R1011-2)") (class "Default")
      (node (ref "R1011") (pin "0") (pinfunction "2_0") (pintype "passive"))
      (node (ref "R1012") (pin "0") (pinfunction "2_0") (pintype "passive"))
      (node (ref "R1013") (pin "0") (pinfunction "2_0") (pintype "passive"))
    )
    (net (code "81") (name "Net-(R1012-1)") (class "Default")
      (node (ref "R1012") (pin "0") (pinfunction "1_0") (pintype "passive"))
      (node (ref "R1015") (pin "0") (pinfunction "2_0") (pintype "passive"))
    )
    (net (code "82") (name "Net-(R1013-1)") (class "Default")
      (node (ref "R1013") (pin "0") (pinfunction "1_0") (pintype "passive"))
      (node (ref "R1014") (pin "0") (pinfunction "2_0") (pintype "passive"))
    )
    (net (code "83") (name "Net-(R2028-2)") (class "Default")
      (node (ref "R2028") (pin "0") (pinfunction "2_0") (pintype "passive"))
      (node (ref "U702") (pin "0") (pinfunction "OUT0B_0") (pintype "passive"))
    )
    (net (code "84") (name "Net-(R2029-2)") (class "Default")
      (node (ref "R2029") (pin "0") (pinfunction "2_0") (pintype "passive"))
      (node (ref "R2030") (pin "0") (pinfunction "1_0") (pintype "passive"))
      (node (ref "X2") (pin "0") (pinfunction "ENB/TUNE_0") (pintype "passive"))
    )
    (net (code "85") (name "unconnected-(GENERIC-POWER-20-1-Pad0)") (class "Default")
      (node (ref "GENERIC-POWER-20") (pin "0") (pinfunction "1_0") (pintype "passive"))
    )
    (net (code "86") (name "unconnected-(R903-2-Pad0)") (class "Default")
      (node (ref "R903") (pin "0") (pinfunction "2_0") (pintype "passive"))
    )
    (net (code "87") (name "unconnected-(U101-9-CLK2-Pad0)") (class "Default")
      (node (ref "U101-9") (pin "0") (pinfunction "CLK2_0") (pintype "passive"))
    )
    (net (code "88") (name "unconnected-(U101-9-CLK3-Pad0)") (class "Default")
      (node (ref "U101-9") (pin "0") (pinfunction "CLK3_0") (pintype "passive"))
    )
    (net (code "89") (name "unconnected-(U101-9-PLL2_OUTN{slash}IO-Pad0)") (class "Default")
      (node (ref "U101-9") (pin "0") (pinfunction "PLL2_OUTN/IO_0") (pintype "passive"))
    )
    (net (code "90") (name "unconnected-(U101-9-PLL2_OUTP{slash}IO-Pad0)") (class "Default")
      (node (ref "U101-9") (pin "0") (pinfunction "PLL2_OUTP/IO_0") (pintype "passive"))
    )
    (net (code "91") (name "unconnected-(U101-CLK0-Pad0)") (class "Default")
      (node (ref "U101") (pin "0") (pinfunction "CLK0_0") (pintype "passive"))
    )
    (net (code "92") (name "unconnected-(U101-CLK1-Pad0)") (class "Default")
      (node (ref "U101") (pin "0") (pinfunction "CLK1_0") (pintype "passive"))
    )
    (net (code "93") (name "unconnected-(U101-PLL1_OUTN{slash}IO-Pad0)") (class "Default")
      (node (ref "U101") (pin "0") (pinfunction "PLL1_OUTN/IO_0") (pintype "passive"))
    )
    (net (code "94") (name "unconnected-(U101-PLL1_OUTP{slash}IO-Pad0)") (class "Default")
      (node (ref "U101") (pin "0") (pinfunction "PLL1_OUTP/IO_0") (pintype "passive"))
    )
    (net (code "95") (name "unconnected-(U601-CLKOUT1-Pad0)") (class "Default")
      (node (ref "U601") (pin "0") (pinfunction "CLKOUT1_0") (pintype "passive"))
    )
    (net (code "96") (name "unconnected-(U601-CLKOUT2-Pad0)") (class "Default")
      (node (ref "U601") (pin "0") (pinfunction "CLKOUT2_0") (pintype "passive"))
    )
    (net (code "97") (name "unconnected-(U601-DLL_LOCK-Pad0)") (class "Default")
      (node (ref "U601") (pin "0") (pinfunction "DLL_LOCK_0") (pintype "passive"))
    )
    (net (code "98") (name "unconnected-(U601-NC-Pad0)") (class "Default")
      (node (ref "U601") (pin "0") (pinfunction "NC_0") (pintype "passive"))
    )
    (net (code "99") (name "unconnected-(U601-OSC1-Pad0)") (class "Default")
      (node (ref "U601") (pin "0") (pinfunction "OSC1_0") (pintype "passive"))
    )
    (net (code "100") (name "unconnected-(U601-OSC2-Pad0)") (class "Default")
      (node (ref "U601") (pin "0") (pinfunction "OSC2_0") (pintype "passive"))
    )
    (net (code "101") (name "unconnected-(U602-CLKOUT1-Pad0)") (class "Default")
      (node (ref "U602") (pin "0") (pinfunction "CLKOUT1_0") (pintype "passive"))
    )
    (net (code "102") (name "unconnected-(U602-CLKOUT2-Pad0)") (class "Default")
      (node (ref "U602") (pin "0") (pinfunction "CLKOUT2_0") (pintype "passive"))
    )
    (net (code "103") (name "unconnected-(U602-DLL_LOCK-Pad0)") (class "Default")
      (node (ref "U602") (pin "0") (pinfunction "DLL_LOCK_0") (pintype "passive"))
    )
    (net (code "104") (name "unconnected-(U602-NC-Pad0)") (class "Default")
      (node (ref "U602") (pin "0") (pinfunction "NC_0") (pintype "passive"))
    )
    (net (code "105") (name "unconnected-(U602-OSC1-Pad0)") (class "Default")
      (node (ref "U602") (pin "0") (pinfunction "OSC1_0") (pintype "passive"))
    )
    (net (code "106") (name "unconnected-(U602-OSC2-Pad0)") (class "Default")
      (node (ref "U602") (pin "0") (pinfunction "OSC2_0") (pintype "passive"))
    )
    (net (code "107") (name "unconnected-(U702-15-RSET-Pad0)") (class "Default")
      (node (ref "U702-15") (pin "0") (pinfunction "RSET_0") (pintype "passive"))
    )
    (net (code "108") (name "unconnected-(U702-OUT0-Pad0)") (class "Default")
      (node (ref "U702") (pin "0") (pinfunction "OUT0_0") (pintype "passive"))
    )
    (net (code "109") (name "unconnected-(U702-OUT1-Pad0)") (class "Default")
      (node (ref "U702") (pin "0") (pinfunction "OUT1_0") (pintype "passive"))
    )
    (net (code "110") (name "unconnected-(U702-OUT1B-Pad0)") (class "Default")
      (node (ref "U702") (pin "0") (pinfunction "OUT1B_0") (pintype "passive"))
    )
    (net (code "111") (name "unconnected-(U702-OUT2-Pad0)") (class "Default")
      (node (ref "U702") (pin "0") (pinfunction "OUT2_0") (pintype "passive"))
    )
    (net (code "112") (name "unconnected-(U702-OUT2B-Pad0)") (class "Default")
      (node (ref "U702") (pin "0") (pinfunction "OUT2B_0") (pintype "passive"))
    )
    (net (code "113") (name "unconnected-(U702-SYNCB-Pad0)") (class "Default")
      (node (ref "U702") (pin "0") (pinfunction "SYNCB_0") (pintype "passive"))
    )
  )
)
